# LM117_LDO_module.net
KiCad netlist of a schematic drawn in EAGLE
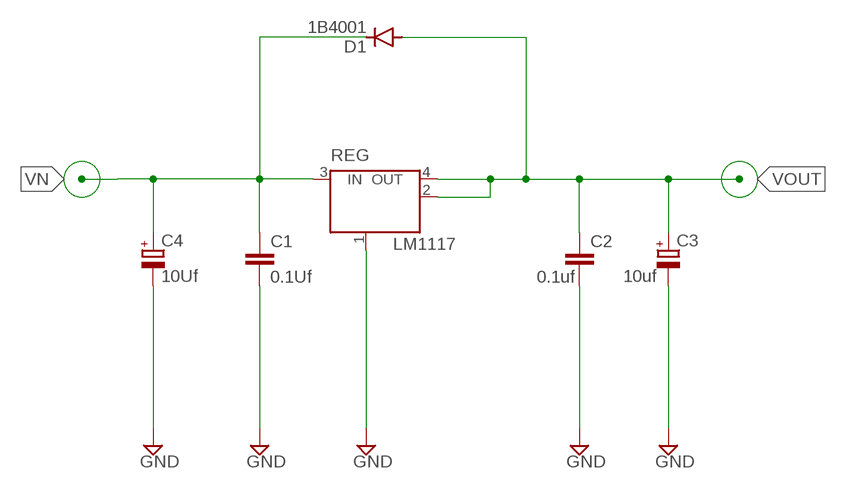
[diagram p0: schematic, sheet 1]

(export (version "E")
  (design (tool "Eeschema 10.0.6"))
  (components
    (comp (ref "C1")
      (value "0.1Uf")
      (footprint "eagle-import:C1206")
      (libsource (lib "eagle-import") (part "C-EUC1206"))
    )
    (comp (ref "C2")
      (value "0.1uf")
      (footprint "eagle-import:C1206")
      (libsource (lib "eagle-import") (part "C-EUC1206"))
    )
    (comp (ref "C3")
      (value "10uf")
      (footprint "eagle-import:CT3216")
      (libsource (lib "eagle-import") (part "CPOL-EUCT3216"))
    )
    (comp (ref "C4")
      (value "10Uf")
      (footprint "eagle-import:CT3216")
      (libsource (lib "eagle-import") (part "CPOL-EUCT3216"))
    )
    (comp (ref "D1")
      (value "1B4001")
      (footprint "eagle-import:DO-214AC")
      (libsource (lib "eagle-import") (part "DIODE-DO-214AC"))
    )
    (comp (ref "REG")
      (value "LM1117")
      (footprint "eagle-import:SOT223")
      (libsource (lib "eagle-import") (part "MC33269ST-3.3T3"))
    )
  )
  (nets
    (net (code "1") (name "GND") (class "Default")
      (node (ref "C1") (pin "2") (pinfunction "2_2") (pintype "passive"))
      (node (ref "C2") (pin "2") (pinfunction "2_2") (pintype "passive"))
      (node (ref "C3") (pin "-") (pinfunction "-_-") (pintype "passive"))
      (node (ref "C4") (pin "-") (pinfunction "-_-") (pintype "passive"))
      (node (ref "REG") (pin "1") (pinfunction "GND/ADJ_1") (pintype "input"))
    )
    (net (code "2") (name "VN") (class "Default")
      (node (ref "C1") (pin "1") (pinfunction "1_1") (pintype "passive"))
      (node (ref "C4") (pin "+") (pinfunction "+_+") (pintype "passive"))
      (node (ref "D1") (pin "C") (pinfunction "C_C") (pintype "passive"))
      (node (ref "REG") (pin "3") (pinfunction "IN_3") (pintype "input"))
    )
    (net (code "3") (name "VOUT") (class "Default")
      (node (ref "C2") (pin "1") (pinfunction "1_1") (pintype "passive"))
      (node (ref "C3") (pin "+") (pinfunction "+_+") (pintype "passive"))
      (node (ref "D1") (pin "A") (pinfunction "A_A") (pintype "passive"))
      (node (ref "REG") (pin "2") (pinfunction "OUT_2") (pintype "passive"))
      (node (ref "REG") (pin "4") (pinfunction "OUT_4") (pintype "passive"))
    )
  )
)
